# ROM-el_HN61256_v2.net
KiCad netlist of a schematic drawn in EAGLE
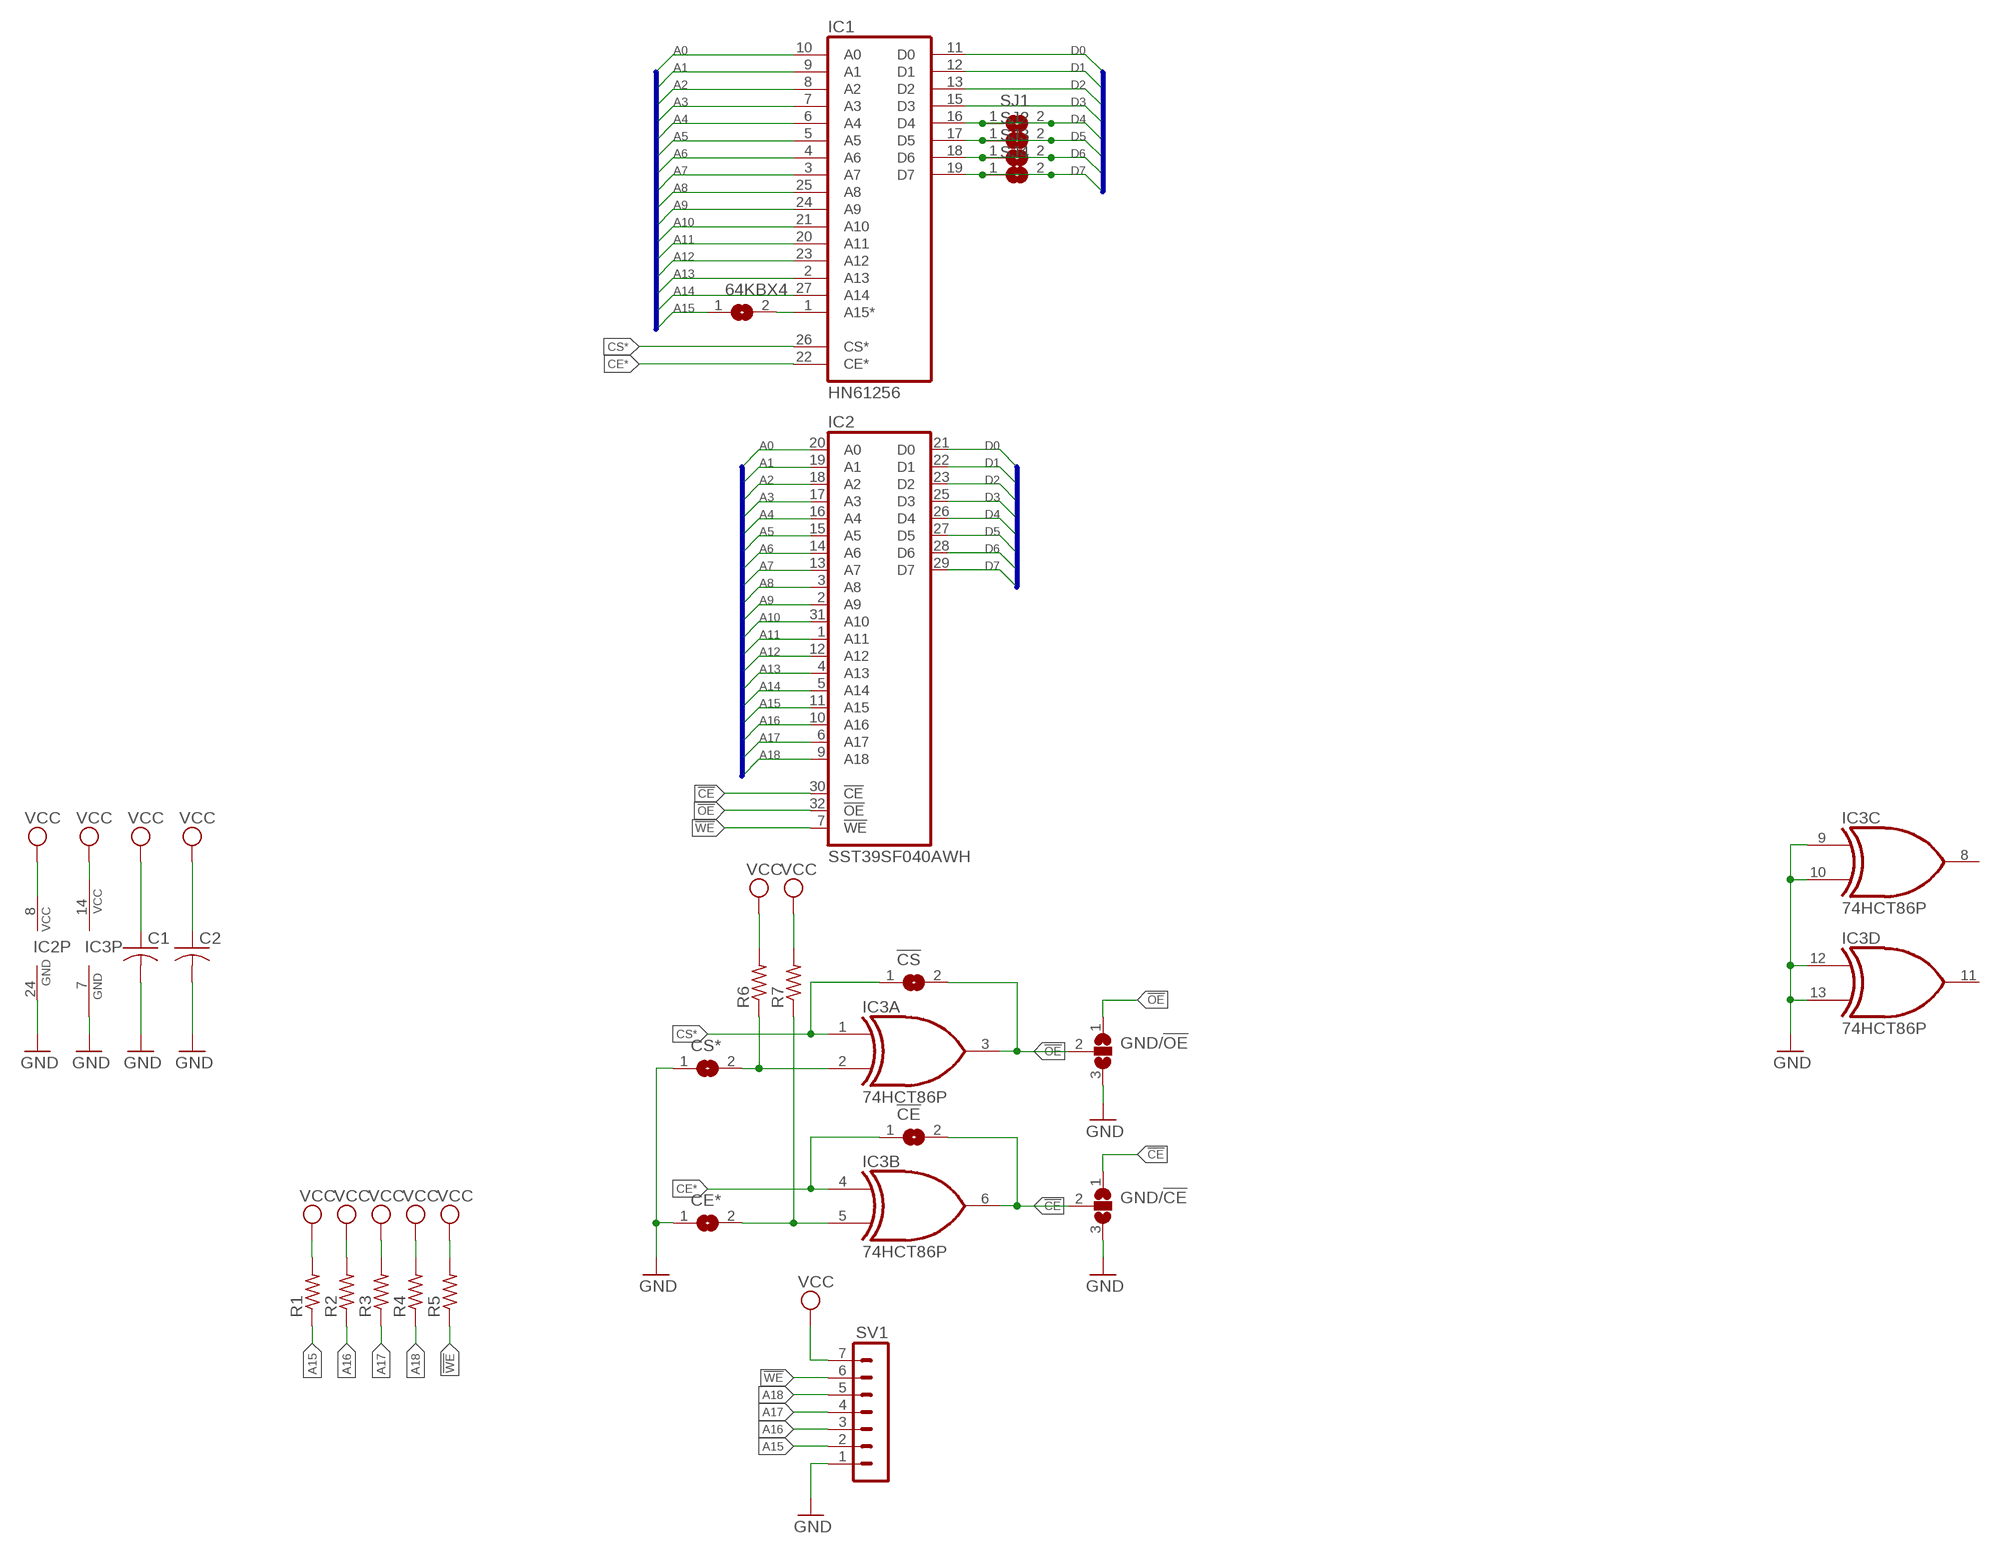
[diagram p0: schematic, sheet 1]

(export (version "E")
  (design (tool "Eeschema 10.0.6"))
  (components
    (comp (ref "!CE") (value "SJ") (footprint "eagle-import:SJ") (libsource (lib "eagle-import") (part "SJ")))
    (comp (ref "!CS") (value "SJ") (footprint "eagle-import:SJ") (libsource (lib "eagle-import") (part "SJ")))
    (comp (ref "64KBX4")
      (value "SJ")
      (footprint "eagle-import:SJ")
      (libsource (lib "eagle-import") (part "SJ"))
    )
    (comp (ref "C1")
      (value "C-USC0402")
      (footprint "eagle-import:C0402")
      (libsource (lib "eagle-import") (part "C-USC0402"))
    )
    (comp (ref "C2")
      (value "C-USC0402")
      (footprint "eagle-import:C0402")
      (libsource (lib "eagle-import") (part "C-USC0402"))
    )
    (comp (ref "CE*") (value "SJ") (footprint "eagle-import:SJ") (libsource (lib "eagle-import") (part "SJ")))
    (comp (ref "CS*") (value "SJ") (footprint "eagle-import:SJ") (libsource (lib "eagle-import") (part "SJ")))
    (comp (ref "GND/!CE")
      (value "SJ2W")
      (footprint "eagle-import:SJ_2")
      (libsource (lib "eagle-import") (part "SJ2W"))
    )
    (comp (ref "GND/!OE")
      (value "SJ2W")
      (footprint "eagle-import:SJ_2")
      (libsource (lib "eagle-import") (part "SJ2W"))
    )
    (comp (ref "IC1")
      (value "HN61256")
      (footprint "eagle-import:DIL28-6")
      (libsource (lib "eagle-import") (part "HN61256"))
    )
    (comp (ref "IC2")
      (value "SST39SF040AWH")
      (footprint "eagle-import:VSOP32")
      (libsource (lib "eagle-import") (part "SST39SF040AWH"))
    )
    (comp (ref "IC3")
      (value "74HCT86P")
      (footprint "eagle-import:TSSOP14")
      (libsource (lib "eagle-import") (part "7486PHCT"))
    )
    (comp (ref "R1")
      (value "R-US_R0402")
      (footprint "eagle-import:R0402")
      (libsource (lib "eagle-import") (part "R-US_R0402"))
    )
    (comp (ref "R2")
      (value "R-US_R0402")
      (footprint "eagle-import:R0402")
      (libsource (lib "eagle-import") (part "R-US_R0402"))
    )
    (comp (ref "R3")
      (value "R-US_R0402")
      (footprint "eagle-import:R0402")
      (libsource (lib "eagle-import") (part "R-US_R0402"))
    )
    (comp (ref "R4")
      (value "R-US_R0402")
      (footprint "eagle-import:R0402")
      (libsource (lib "eagle-import") (part "R-US_R0402"))
    )
    (comp (ref "R5")
      (value "R-US_R0402")
      (footprint "eagle-import:R0402")
      (libsource (lib "eagle-import") (part "R-US_R0402"))
    )
    (comp (ref "R6")
      (value "R-US_R0402")
      (footprint "eagle-import:R0402")
      (libsource (lib "eagle-import") (part "R-US_R0402"))
    )
    (comp (ref "R7")
      (value "R-US_R0402")
      (footprint "eagle-import:R0402")
      (libsource (lib "eagle-import") (part "R-US_R0402"))
    )
    (comp (ref "SJ1") (value "SJ") (footprint "eagle-import:SJ") (libsource (lib "eagle-import") (part "SJ")))
    (comp (ref "SJ2") (value "SJ") (footprint "eagle-import:SJ") (libsource (lib "eagle-import") (part "SJ")))
    (comp (ref "SJ3") (value "SJ") (footprint "eagle-import:SJ") (libsource (lib "eagle-import") (part "SJ")))
    (comp (ref "SJ4") (value "SJ") (footprint "eagle-import:SJ") (libsource (lib "eagle-import") (part "SJ")))
    (comp (ref "SV1")
      (value "MA07-1")
      (footprint "eagle-import:MA07-1")
      (libsource (lib "eagle-import") (part "MA07-1"))
    )
  )
  (nets
    (net (code "1") (name "/A0") (class "Default")
      (node (ref "IC1") (pin "10") (pinfunction "A0_10") (pintype "input"))
      (node (ref "IC2") (pin "20") (pinfunction "A0_20") (pintype "input"))
    )
    (net (code "2") (name "/A1") (class "Default")
      (node (ref "IC1") (pin "9") (pinfunction "A1_9") (pintype "input"))
      (node (ref "IC2") (pin "19") (pinfunction "A1_19") (pintype "input"))
    )
    (net (code "3") (name "/A2") (class "Default")
      (node (ref "IC1") (pin "8") (pinfunction "A2_8") (pintype "input"))
      (node (ref "IC2") (pin "18") (pinfunction "A2_18") (pintype "input"))
    )
    (net (code "4") (name "/A3") (class "Default")
      (node (ref "IC1") (pin "7") (pinfunction "A3_7") (pintype "input"))
      (node (ref "IC2") (pin "17") (pinfunction "A3_17") (pintype "input"))
    )
    (net (code "5") (name "/A4") (class "Default")
      (node (ref "IC1") (pin "6") (pinfunction "A4_6") (pintype "input"))
      (node (ref "IC2") (pin "16") (pinfunction "A4_16") (pintype "input"))
    )
    (net (code "6") (name "/A5") (class "Default")
      (node (ref "IC1") (pin "5") (pinfunction "A5_5") (pintype "input"))
      (node (ref "IC2") (pin "15") (pinfunction "A5_15") (pintype "input"))
    )
    (net (code "7") (name "/A6") (class "Default")
      (node (ref "IC1") (pin "4") (pinfunction "A6_4") (pintype "input"))
      (node (ref "IC2") (pin "14") (pinfunction "A6_14") (pintype "input"))
    )
    (net (code "8") (name "/A7") (class "Default")
      (node (ref "IC1") (pin "3") (pinfunction "A7_3") (pintype "input"))
      (node (ref "IC2") (pin "13") (pinfunction "A7_13") (pintype "input"))
    )
    (net (code "9") (name "/A8") (class "Default")
      (node (ref "IC1") (pin "25") (pinfunction "A8_25") (pintype "input"))
      (node (ref "IC2") (pin "3") (pinfunction "A8_3") (pintype "input"))
    )
    (net (code "10") (name "/A9") (class "Default")
      (node (ref "IC1") (pin "24") (pinfunction "A9_24") (pintype "input"))
      (node (ref "IC2") (pin "2") (pinfunction "A9_2") (pintype "input"))
    )
    (net (code "11") (name "/A10") (class "Default")
      (node (ref "IC1") (pin "21") (pinfunction "A10_21") (pintype "input"))
      (node (ref "IC2") (pin "31") (pinfunction "A10_31") (pintype "input"))
    )
    (net (code "12") (name "/A11") (class "Default")
      (node (ref "IC1") (pin "20") (pinfunction "A11_20") (pintype "input"))
      (node (ref "IC2") (pin "1") (pinfunction "A11_1") (pintype "input"))
    )
    (net (code "13") (name "/A12") (class "Default")
      (node (ref "IC1") (pin "23") (pinfunction "A12_23") (pintype "input"))
      (node (ref "IC2") (pin "12") (pinfunction "A12_12") (pintype "input"))
    )
    (net (code "14") (name "/A13") (class "Default")
      (node (ref "IC1") (pin "2") (pinfunction "A13_2") (pintype "input"))
      (node (ref "IC2") (pin "4") (pinfunction "A13_4") (pintype "input"))
    )
    (net (code "15") (name "/A14") (class "Default")
      (node (ref "IC1") (pin "27") (pinfunction "A14_27") (pintype "input"))
      (node (ref "IC2") (pin "5") (pinfunction "A14_5") (pintype "input"))
    )
    (net (code "16") (name "/D0") (class "Default")
      (node (ref "IC1") (pin "11") (pinfunction "D0_11") (pintype "bidirectional"))
      (node (ref "IC2") (pin "21") (pinfunction "D0_21") (pintype "bidirectional"))
    )
    (net (code "17") (name "/D1") (class "Default")
      (node (ref "IC1") (pin "12") (pinfunction "D1_12") (pintype "bidirectional"))
      (node (ref "IC2") (pin "22") (pinfunction "D1_22") (pintype "bidirectional"))
    )
    (net (code "18") (name "/D2") (class "Default")
      (node (ref "IC1") (pin "13") (pinfunction "D2_13") (pintype "bidirectional"))
      (node (ref "IC2") (pin "23") (pinfunction "D2_23") (pintype "bidirectional"))
    )
    (net (code "19") (name "/D3") (class "Default")
      (node (ref "IC1") (pin "15") (pinfunction "D3_15") (pintype "bidirectional"))
      (node (ref "IC2") (pin "25") (pinfunction "D3_25") (pintype "bidirectional"))
    )
    (net (code "20") (name "/D4") (class "Default")
      (node (ref "IC1") (pin "16") (pinfunction "D4_16") (pintype "bidirectional"))
      (node (ref "IC2") (pin "26") (pinfunction "D4_26") (pintype "bidirectional"))
      (node (ref "SJ1") (pin "1") (pinfunction "1_1") (pintype "passive"))
      (node (ref "SJ1") (pin "2") (pinfunction "2_2") (pintype "passive"))
    )
    (net (code "21") (name "/D5") (class "Default")
      (node (ref "IC1") (pin "17") (pinfunction "D5_17") (pintype "bidirectional"))
      (node (ref "IC2") (pin "27") (pinfunction "D5_27") (pintype "bidirectional"))
      (node (ref "SJ2") (pin "1") (pinfunction "1_1") (pintype "passive"))
      (node (ref "SJ2") (pin "2") (pinfunction "2_2") (pintype "passive"))
    )
    (net (code "22") (name "/D6") (class "Default")
      (node (ref "IC1") (pin "18") (pinfunction "D6_18") (pintype "bidirectional"))
      (node (ref "IC2") (pin "28") (pinfunction "D6_28") (pintype "bidirectional"))
      (node (ref "SJ3") (pin "1") (pinfunction "1_1") (pintype "passive"))
      (node (ref "SJ3") (pin "2") (pinfunction "2_2") (pintype "passive"))
    )
    (net (code "23") (name "/D7") (class "Default")
      (node (ref "IC1") (pin "19") (pinfunction "D7_19") (pintype "bidirectional"))
      (node (ref "IC2") (pin "29") (pinfunction "D7_29") (pintype "bidirectional"))
      (node (ref "SJ4") (pin "1") (pinfunction "1_1") (pintype "passive"))
      (node (ref "SJ4") (pin "2") (pinfunction "2_2") (pintype "passive"))
    )
    (net (code "24") (name "/~{CE}") (class "Default")
      (node (ref "!CE") (pin "2") (pinfunction "2_2") (pintype "passive"))
      (node (ref "GND/!CE") (pin "1") (pinfunction "1_1") (pintype "passive"))
      (node (ref "GND/!CE") (pin "2") (pinfunction "2_2") (pintype "passive"))
      (node (ref "IC2") (pin "30") (pinfunction "~{CE}_30") (pintype "input"))
      (node (ref "IC3") (pin "6") (pinfunction "O_6") (pintype "output"))
    )
    (net (code "25") (name "/~{OE}") (class "Default")
      (node (ref "!CS") (pin "2") (pinfunction "2_2") (pintype "passive"))
      (node (ref "GND/!OE") (pin "1") (pinfunction "1_1") (pintype "passive"))
      (node (ref "GND/!OE") (pin "2") (pinfunction "2_2") (pintype "passive"))
      (node (ref "IC2") (pin "32") (pinfunction "~{OE}_32") (pintype "input"))
      (node (ref "IC3") (pin "3") (pinfunction "O_3") (pintype "output"))
    )
    (net (code "26") (name "/~{WE}") (class "Default")
      (node (ref "IC2") (pin "7") (pinfunction "~{WE}_7") (pintype "input"))
      (node (ref "R5") (pin "1") (pinfunction "1_1") (pintype "passive"))
      (node (ref "SV1") (pin "6") (pinfunction "6_6") (pintype "passive"))
    )
    (net (code "27") (name "A15") (class "Default")
      (node (ref "64KBX4") (pin "1") (pinfunction "1_1") (pintype "passive"))
      (node (ref "IC2") (pin "11") (pinfunction "A15_11") (pintype "input"))
      (node (ref "R1") (pin "1") (pinfunction "1_1") (pintype "passive"))
      (node (ref "SV1") (pin "2") (pinfunction "2_2") (pintype "passive"))
    )
    (net (code "28") (name "A16") (class "Default")
      (node (ref "IC2") (pin "10") (pinfunction "A16_10") (pintype "input"))
      (node (ref "R2") (pin "1") (pinfunction "1_1") (pintype "passive"))
      (node (ref "SV1") (pin "3") (pinfunction "3_3") (pintype "passive"))
    )
    (net (code "29") (name "A17") (class "Default")
      (node (ref "IC2") (pin "6") (pinfunction "A17_6") (pintype "input"))
      (node (ref "R3") (pin "1") (pinfunction "1_1") (pintype "passive"))
      (node (ref "SV1") (pin "4") (pinfunction "4_4") (pintype "passive"))
    )
    (net (code "30") (name "A18") (class "Default")
      (node (ref "IC2") (pin "9") (pinfunction "A18_9") (pintype "input"))
      (node (ref "R4") (pin "1") (pinfunction "1_1") (pintype "passive"))
      (node (ref "SV1") (pin "5") (pinfunction "5_5") (pintype "passive"))
    )
    (net (code "31") (name "CE*") (class "Default")
      (node (ref "!CE") (pin "1") (pinfunction "1_1") (pintype "passive"))
      (node (ref "IC1") (pin "22") (pinfunction "CE*_22") (pintype "input"))
      (node (ref "IC3") (pin "4") (pinfunction "I0_4") (pintype "input"))
    )
    (net (code "32") (name "CS*") (class "Default")
      (node (ref "!CS") (pin "1") (pinfunction "1_1") (pintype "passive"))
      (node (ref "IC1") (pin "26") (pinfunction "CS*_26") (pintype "input"))
      (node (ref "IC3") (pin "1") (pinfunction "I0_1") (pintype "input"))
    )
    (net (code "33") (name "GND") (class "Default")
      (node (ref "C1") (pin "2") (pinfunction "2_2") (pintype "passive"))
      (node (ref "C2") (pin "2") (pinfunction "2_2") (pintype "passive"))
      (node (ref "CE*") (pin "1") (pinfunction "1_1") (pintype "passive"))
      (node (ref "CS*") (pin "1") (pinfunction "1_1") (pintype "passive"))
      (node (ref "GND/!CE") (pin "3") (pinfunction "3_3") (pintype "passive"))
      (node (ref "GND/!OE") (pin "3") (pinfunction "3_3") (pintype "passive"))
      (node (ref "IC2") (pin "24") (pinfunction "GND_24") (pintype "power_in"))
      (node (ref "IC3") (pin "10") (pinfunction "I1_10") (pintype "input"))
      (node (ref "IC3") (pin "12") (pinfunction "I0_12") (pintype "input"))
      (node (ref "IC3") (pin "13") (pinfunction "I1_13") (pintype "input"))
      (node (ref "IC3") (pin "7") (pinfunction "GND_7") (pintype "power_in"))
      (node (ref "IC3") (pin "9") (pinfunction "I0_9") (pintype "input"))
      (node (ref "SV1") (pin "1") (pinfunction "1_1") (pintype "passive"))
    )
    (net (code "34") (name "Net-(IC1A-A15*)") (class "Default")
      (node (ref "64KBX4") (pin "2") (pinfunction "2_2") (pintype "passive"))
      (node (ref "IC1") (pin "1") (pinfunction "A15*_1") (pintype "input"))
    )
    (net (code "35") (name "Net-(IC3A-I1)") (class "Default")
      (node (ref "CS*") (pin "2") (pinfunction "2_2") (pintype "passive"))
      (node (ref "IC3") (pin "2") (pinfunction "I1_2") (pintype "input"))
      (node (ref "R6") (pin "1") (pinfunction "1_1") (pintype "passive"))
    )
    (net (code "36") (name "Net-(IC3B-I1)") (class "Default")
      (node (ref "CE*") (pin "2") (pinfunction "2_2") (pintype "passive"))
      (node (ref "IC3") (pin "5") (pinfunction "I1_5") (pintype "input"))
      (node (ref "R7") (pin "1") (pinfunction "1_1") (pintype "passive"))
    )
    (net (code "37") (name "VCC") (class "Default")
      (node (ref "C1") (pin "1") (pinfunction "1_1") (pintype "passive"))
      (node (ref "C2") (pin "1") (pinfunction "1_1") (pintype "passive"))
      (node (ref "IC2") (pin "8") (pinfunction "VCC_8") (pintype "power_in"))
      (node (ref "IC3") (pin "14") (pinfunction "VCC_14") (pintype "power_in"))
      (node (ref "R1") (pin "2") (pinfunction "2_2") (pintype "passive"))
      (node (ref "R2") (pin "2") (pinfunction "2_2") (pintype "passive"))
      (node (ref "R3") (pin "2") (pinfunction "2_2") (pintype "passive"))
      (node (ref "R4") (pin "2") (pinfunction "2_2") (pintype "passive"))
      (node (ref "R5") (pin "2") (pinfunction "2_2") (pintype "passive"))
      (node (ref "R6") (pin "2") (pinfunction "2_2") (pintype "passive"))
      (node (ref "R7") (pin "2") (pinfunction "2_2") (pintype "passive"))
      (node (ref "SV1") (pin "7") (pinfunction "7_7") (pintype "passive"))
    )
    (net (code "38") (name "unconnected-(IC3C-O-Pad8)") (class "Default")
      (node (ref "IC3") (pin "8") (pinfunction "O_8") (pintype "output"))
    )
    (net (code "39") (name "unconnected-(IC3D-O-Pad11)") (class "Default")
      (node (ref "IC3") (pin "11") (pinfunction "O_11") (pintype "output"))
    )
  )
)
